# Teensy4_1.net
KiCad netlist of a schematic drawn in Altium Designer
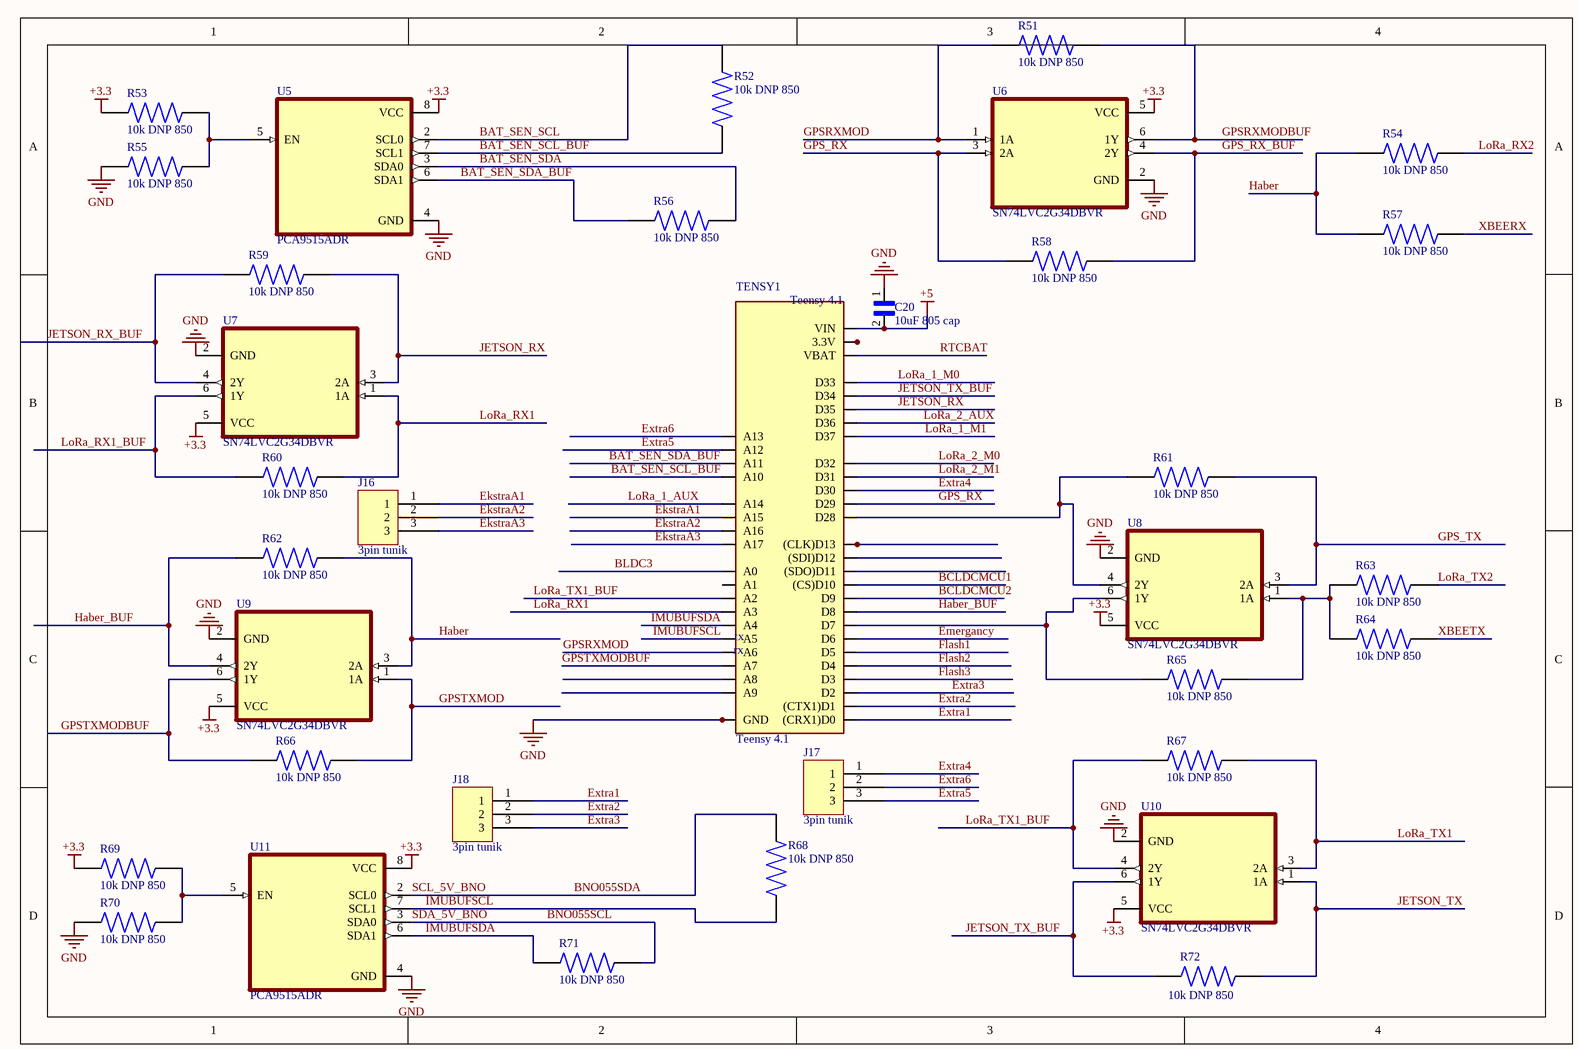
[diagram p0: Teensy4.1.SchDoc]

(export (version "E")
  (design (tool "Eeschema 10.0.6"))
  (components
    (comp (ref "C20")
      (value "10uF 805 cap")
      (footprint "1uF 805 Cap")
      (libsource (lib "iee_altium") (part "1uF 805 cap"))
    )
    (comp (ref "J16")
      (value "3pin tunik")
      (footprint "3pin tunik")
      (libsource (lib "iee_altium") (part "3pin tunik"))
    )
    (comp (ref "J17")
      (value "3pin tunik")
      (footprint "3pin tunik")
      (libsource (lib "iee_altium") (part "3pin tunik"))
    )
    (comp (ref "J18")
      (value "3pin tunik")
      (footprint "3pin tunik")
      (libsource (lib "iee_altium") (part "3pin tunik"))
    )
    (comp (ref "R51")
      (value "10k DNP 850")
      (footprint "10k 850")
      (libsource (lib "iee_altium") (part "10k 850"))
    )
    (comp (ref "R52")
      (value "10k DNP 850")
      (footprint "10k 850")
      (libsource (lib "iee_altium") (part "10k 850"))
    )
    (comp (ref "R53")
      (value "10k DNP 850")
      (footprint "10k 850")
      (libsource (lib "iee_altium") (part "10k 850"))
    )
    (comp (ref "R54")
      (value "10k DNP 850")
      (footprint "10k 850")
      (libsource (lib "iee_altium") (part "10k 850"))
    )
    (comp (ref "R55")
      (value "10k DNP 850")
      (footprint "10k 850")
      (libsource (lib "iee_altium") (part "10k 850"))
    )
    (comp (ref "R56")
      (value "10k DNP 850")
      (footprint "10k 850")
      (libsource (lib "iee_altium") (part "10k 850"))
    )
    (comp (ref "R57")
      (value "10k DNP 850")
      (footprint "10k 850")
      (libsource (lib "iee_altium") (part "10k 850"))
    )
    (comp (ref "R58")
      (value "10k DNP 850")
      (footprint "10k 850")
      (libsource (lib "iee_altium") (part "10k 850"))
    )
    (comp (ref "R59")
      (value "10k DNP 850")
      (footprint "10k 850")
      (libsource (lib "iee_altium") (part "10k 850"))
    )
    (comp (ref "R60")
      (value "10k DNP 850")
      (footprint "10k 850")
      (libsource (lib "iee_altium") (part "10k 850"))
    )
    (comp (ref "R61")
      (value "10k DNP 850")
      (footprint "10k 850")
      (libsource (lib "iee_altium") (part "10k 850"))
    )
    (comp (ref "R62")
      (value "10k DNP 850")
      (footprint "10k 850")
      (libsource (lib "iee_altium") (part "10k 850"))
    )
    (comp (ref "R63")
      (value "10k DNP 850")
      (footprint "10k 850")
      (libsource (lib "iee_altium") (part "10k 850"))
    )
    (comp (ref "R64")
      (value "10k DNP 850")
      (footprint "10k 850")
      (libsource (lib "iee_altium") (part "10k 850"))
    )
    (comp (ref "R65")
      (value "10k DNP 850")
      (footprint "10k 850")
      (libsource (lib "iee_altium") (part "10k 850"))
    )
    (comp (ref "R66")
      (value "10k DNP 850")
      (footprint "10k 850")
      (libsource (lib "iee_altium") (part "10k 850"))
    )
    (comp (ref "R67")
      (value "10k DNP 850")
      (footprint "10k 850")
      (libsource (lib "iee_altium") (part "10k 850"))
    )
    (comp (ref "R68")
      (value "10k DNP 850")
      (footprint "10k 850")
      (libsource (lib "iee_altium") (part "10k 850"))
    )
    (comp (ref "R69")
      (value "10k DNP 850")
      (footprint "10k 850")
      (libsource (lib "iee_altium") (part "10k 850"))
    )
    (comp (ref "R70")
      (value "10k DNP 850")
      (footprint "10k 850")
      (libsource (lib "iee_altium") (part "10k 850"))
    )
    (comp (ref "R71")
      (value "10k DNP 850")
      (footprint "10k 850")
      (libsource (lib "iee_altium") (part "10k 850"))
    )
    (comp (ref "R72")
      (value "10k DNP 850")
      (footprint "10k 850")
      (libsource (lib "iee_altium") (part "10k 850"))
    )
    (comp (ref "TENSY1")
      (value "Teensy 4.1")
      (footprint "Teensy 4.1")
      (libsource (lib "IEEE_altium") (part "Teensy 4.1"))
    )
    (comp (ref "U5")
      (value "PCA9515ADR")
      (footprint "SOIC127P599X175-8N")
      (description "Dual Bidirectional I2C Bus and SMBus Repeater 8-SOIC -40 to 85")
      (fields (field (name "MF") "Texas Instruments"))
      (libsource (lib "iee_altium") (part "PCA9515ADR"))
    )
    (comp (ref "U6")
      (value "SN74LVC2G34DBVR")
      (footprint "SOT95P280X145-6N")
      (description "2-ch, 1.65-V to 5.5-V buffers")
      (fields (field (name "MF") "Texas Instruments"))
      (libsource (lib "") (part "SN74LVC2G34DBVR_1"))
    )
    (comp (ref "U7")
      (value "SN74LVC2G34DBVR")
      (footprint "SOT95P280X145-6N")
      (description "2-ch, 1.65-V to 5.5-V buffers")
      (fields (field (name "MF") "Texas Instruments"))
      (libsource (lib "iee_altium") (part "SN74LVC2G34DBVR"))
    )
    (comp (ref "U8")
      (value "SN74LVC2G34DBVR")
      (footprint "SOT95P280X145-6N")
      (description "2-ch, 1.65-V to 5.5-V buffers")
      (fields (field (name "MF") "Texas Instruments"))
      (libsource (lib "iee_altium") (part "SN74LVC2G34DBVR"))
    )
    (comp (ref "U9")
      (value "SN74LVC2G34DBVR")
      (footprint "SOT95P280X145-6N")
      (description "2-ch, 1.65-V to 5.5-V buffers")
      (fields (field (name "MF") "Texas Instruments"))
      (libsource (lib "iee_altium") (part "SN74LVC2G34DBVR"))
    )
    (comp (ref "U10")
      (value "SN74LVC2G34DBVR")
      (footprint "SOT95P280X145-6N")
      (description "2-ch, 1.65-V to 5.5-V buffers")
      (fields (field (name "MF") "Texas Instruments"))
      (libsource (lib "iee_altium") (part "SN74LVC2G34DBVR"))
    )
    (comp (ref "U11")
      (value "PCA9515ADR")
      (footprint "SOIC127P599X175-8N")
      (description "Dual Bidirectional I2C Bus and SMBus Repeater 8-SOIC -40 to 85")
      (fields (field (name "MF") "Texas Instruments"))
      (libsource (lib "iee_altium") (part "PCA9515ADR"))
    )
  )
  (nets
    (net (code "1") (name "+3.3") (class "Default")
      (node (ref "R53") (pin "1") (pinfunction "1_1") (pintype "passive"))
      (node (ref "R69") (pin "1") (pinfunction "1_1") (pintype "passive"))
      (node (ref "U10") (pin "5") (pinfunction "VCC_5") (pintype "power_in"))
      (node (ref "U11") (pin "8") (pinfunction "VCC_8") (pintype "power_in"))
      (node (ref "U5") (pin "8") (pinfunction "VCC_8") (pintype "power_in"))
      (node (ref "U6") (pin "5") (pinfunction "VCC_5") (pintype "power_in"))
      (node (ref "U7") (pin "5") (pinfunction "VCC_5") (pintype "power_in"))
      (node (ref "U8") (pin "5") (pinfunction "VCC_5") (pintype "power_in"))
      (node (ref "U9") (pin "5") (pinfunction "VCC_5") (pintype "power_in"))
    )
    (net (code "2") (name "+5") (class "Default")
      (node (ref "C20") (pin "2") (pinfunction "2_2") (pintype "passive"))
      (node (ref "TENSY1") (pin "VIN") (pinfunction "VIN_VIN") (pintype "power_in"))
    )
    (net (code "3") (name "/BAT_SEN_SCL") (class "Default")
      (node (ref "R52") (pin "1") (pinfunction "1_1") (pintype "passive"))
      (node (ref "U5") (pin "2") (pinfunction "SCL0_2") (pintype "output"))
    )
    (net (code "4") (name "/BAT_SEN_SCL_BUF") (class "Default")
      (node (ref "R52") (pin "2") (pinfunction "2_2") (pintype "passive"))
      (node (ref "TENSY1") (pin "D24") (pinfunction "A10_D24") (pintype "bidirectional"))
      (node (ref "U5") (pin "7") (pinfunction "SCL1_7") (pintype "output"))
    )
    (net (code "5") (name "/BAT_SEN_SDA") (class "Default")
      (node (ref "R56") (pin "2") (pinfunction "2_2") (pintype "passive"))
      (node (ref "U5") (pin "3") (pinfunction "SDA0_3") (pintype "output"))
    )
    (net (code "6") (name "/BAT_SEN_SDA_BUF") (class "Default")
      (node (ref "R56") (pin "1") (pinfunction "1_1") (pintype "passive"))
      (node (ref "TENSY1") (pin "D25") (pinfunction "A11_D25") (pintype "bidirectional"))
      (node (ref "U5") (pin "6") (pinfunction "SDA1_6") (pintype "output"))
    )
    (net (code "7") (name "/BCLDCMCU1") (class "Default")
      (node (ref "TENSY1") (pin "D10") (pinfunction "(CS)D10_D10") (pintype "bidirectional"))
    )
    (net (code "8") (name "/BCLDCMCU2") (class "Default")
      (node (ref "TENSY1") (pin "D9") (pinfunction "D9_D9") (pintype "bidirectional"))
    )
    (net (code "9") (name "/BLDC3") (class "Default")
      (node (ref "TENSY1") (pin "D14") (pinfunction "A0_D14") (pintype "bidirectional"))
    )
    (net (code "10") (name "/BNO055SCL") (class "Default")
      (node (ref "R71") (pin "2") (pinfunction "2_2") (pintype "passive"))
      (node (ref "U11") (pin "3") (pinfunction "SDA0_3") (pintype "output"))
    )
    (net (code "11") (name "/BNO055SDA") (class "Default")
      (node (ref "R68") (pin "1") (pinfunction "1_1") (pintype "passive"))
      (node (ref "U11") (pin "2") (pinfunction "SCL0_2") (pintype "output"))
    )
    (net (code "12") (name "/EkstraA1") (class "Default")
      (node (ref "J16") (pin "1") (pinfunction "1_1") (pintype "passive"))
      (node (ref "TENSY1") (pin "D39") (pinfunction "A15_D39") (pintype "bidirectional"))
    )
    (net (code "13") (name "/EkstraA2") (class "Default")
      (node (ref "J16") (pin "2") (pinfunction "2_2") (pintype "passive"))
      (node (ref "TENSY1") (pin "D40") (pinfunction "A16_D40") (pintype "bidirectional"))
    )
    (net (code "14") (name "/EkstraA3") (class "Default")
      (node (ref "J16") (pin "3") (pinfunction "3_3") (pintype "passive"))
      (node (ref "TENSY1") (pin "D41") (pinfunction "A17_D41") (pintype "bidirectional"))
    )
    (net (code "15") (name "/Emergancy") (class "Default")
      (node (ref "TENSY1") (pin "D6") (pinfunction "D6_D6") (pintype "bidirectional"))
    )
    (net (code "16") (name "/Extra1") (class "Default")
      (node (ref "J18") (pin "1") (pinfunction "1_1") (pintype "passive"))
      (node (ref "TENSY1") (pin "D0") (pinfunction "(CRX1)D0_D0") (pintype "bidirectional"))
    )
    (net (code "17") (name "/Extra2") (class "Default")
      (node (ref "J18") (pin "2") (pinfunction "2_2") (pintype "passive"))
      (node (ref "TENSY1") (pin "D1") (pinfunction "(CTX1)D1_D1") (pintype "bidirectional"))
    )
    (net (code "18") (name "/Extra3") (class "Default")
      (node (ref "J18") (pin "3") (pinfunction "3_3") (pintype "passive"))
      (node (ref "TENSY1") (pin "D2") (pinfunction "D2_D2") (pintype "bidirectional"))
    )
    (net (code "19") (name "/Extra4") (class "Default")
      (node (ref "J17") (pin "1") (pinfunction "1_1") (pintype "passive"))
      (node (ref "TENSY1") (pin "D30") (pinfunction "D30_D30") (pintype "bidirectional"))
    )
    (net (code "20") (name "/Extra5") (class "Default")
      (node (ref "J17") (pin "3") (pinfunction "3_3") (pintype "passive"))
      (node (ref "TENSY1") (pin "D26") (pinfunction "A12_D26") (pintype "bidirectional"))
    )
    (net (code "21") (name "/Extra6") (class "Default")
      (node (ref "J17") (pin "2") (pinfunction "2_2") (pintype "passive"))
      (node (ref "TENSY1") (pin "D27") (pinfunction "A13_D27") (pintype "bidirectional"))
    )
    (net (code "22") (name "/Flash1") (class "Default")
      (node (ref "TENSY1") (pin "D5") (pinfunction "D5_D5") (pintype "bidirectional"))
    )
    (net (code "23") (name "/Flash2") (class "Default")
      (node (ref "TENSY1") (pin "D4") (pinfunction "D4_D4") (pintype "bidirectional"))
    )
    (net (code "24") (name "/Flash3") (class "Default")
      (node (ref "TENSY1") (pin "D3") (pinfunction "D3_D3") (pintype "bidirectional"))
    )
    (net (code "25") (name "/GPSRXMOD") (class "Default")
      (node (ref "R51") (pin "1") (pinfunction "1_1") (pintype "passive"))
      (node (ref "TENSY1") (pin "D20") (pinfunction "A6_D20") (pintype "bidirectional"))
      (node (ref "U6") (pin "1") (pinfunction "1A_1") (pintype "input"))
    )
    (net (code "26") (name "/GPSRXMODBUF") (class "Default")
      (node (ref "R51") (pin "2") (pinfunction "2_2") (pintype "passive"))
      (node (ref "U6") (pin "6") (pinfunction "1Y_6") (pintype "output"))
    )
    (net (code "27") (name "/GPSTXMOD") (class "Default")
      (node (ref "R66") (pin "2") (pinfunction "2_2") (pintype "passive"))
      (node (ref "U9") (pin "1") (pinfunction "1A_1") (pintype "input"))
    )
    (net (code "28") (name "/GPSTXMODBUF") (class "Default")
      (node (ref "R66") (pin "1") (pinfunction "1_1") (pintype "passive"))
      (node (ref "TENSY1") (pin "D21") (pinfunction "A7_D21") (pintype "bidirectional"))
      (node (ref "U9") (pin "6") (pinfunction "1Y_6") (pintype "output"))
    )
    (net (code "29") (name "/GPS_RX") (class "Default")
      (node (ref "R58") (pin "1") (pinfunction "1_1") (pintype "passive"))
      (node (ref "TENSY1") (pin "D29") (pinfunction "D29_D29") (pintype "bidirectional"))
      (node (ref "U6") (pin "3") (pinfunction "2A_3") (pintype "input"))
    )
    (net (code "30") (name "/GPS_RX_BUF") (class "Default")
      (node (ref "R58") (pin "2") (pinfunction "2_2") (pintype "passive"))
      (node (ref "U6") (pin "4") (pinfunction "2Y_4") (pintype "output"))
    )
    (net (code "31") (name "/GPS_TX") (class "Default")
      (node (ref "R61") (pin "2") (pinfunction "2_2") (pintype "passive"))
      (node (ref "U8") (pin "3") (pinfunction "2A_3") (pintype "input"))
    )
    (net (code "32") (name "/Haber") (class "Default")
      (node (ref "R54") (pin "1") (pinfunction "1_1") (pintype "passive"))
      (node (ref "R57") (pin "1") (pinfunction "1_1") (pintype "passive"))
      (node (ref "R62") (pin "2") (pinfunction "2_2") (pintype "passive"))
      (node (ref "U9") (pin "3") (pinfunction "2A_3") (pintype "input"))
    )
    (net (code "33") (name "/Haber_BUF") (class "Default")
      (node (ref "R62") (pin "1") (pinfunction "1_1") (pintype "passive"))
      (node (ref "TENSY1") (pin "D8") (pinfunction "D8_D8") (pintype "bidirectional"))
      (node (ref "U9") (pin "4") (pinfunction "2Y_4") (pintype "output"))
    )
    (net (code "34") (name "/IMUBUFSCL") (class "Default")
      (node (ref "R68") (pin "2") (pinfunction "2_2") (pintype "passive"))
      (node (ref "TENSY1") (pin "D19") (pinfunction "A5_D19") (pintype "bidirectional"))
      (node (ref "U11") (pin "7") (pinfunction "SCL1_7") (pintype "output"))
    )
    (net (code "35") (name "/IMUBUFSDA") (class "Default")
      (node (ref "R71") (pin "1") (pinfunction "1_1") (pintype "passive"))
      (node (ref "TENSY1") (pin "D18") (pinfunction "A4_D18") (pintype "bidirectional"))
      (node (ref "U11") (pin "6") (pinfunction "SDA1_6") (pintype "output"))
    )
    (net (code "36") (name "/JETSON_RX") (class "Default")
      (node (ref "R59") (pin "2") (pinfunction "2_2") (pintype "passive"))
      (node (ref "TENSY1") (pin "D35") (pinfunction "D35_D35") (pintype "bidirectional"))
      (node (ref "U7") (pin "3") (pinfunction "2A_3") (pintype "input"))
    )
    (net (code "37") (name "/JETSON_RX_BUF") (class "Default")
      (node (ref "R59") (pin "1") (pinfunction "1_1") (pintype "passive"))
      (node (ref "U7") (pin "4") (pinfunction "2Y_4") (pintype "output"))
    )
    (net (code "38") (name "/JETSON_TX") (class "Default")
      (node (ref "R72") (pin "2") (pinfunction "2_2") (pintype "passive"))
      (node (ref "U10") (pin "1") (pinfunction "1A_1") (pintype "input"))
    )
    (net (code "39") (name "/JETSON_TX_BUF") (class "Default")
      (node (ref "R72") (pin "1") (pinfunction "1_1") (pintype "passive"))
      (node (ref "TENSY1") (pin "D34") (pinfunction "D34_D34") (pintype "bidirectional"))
      (node (ref "U10") (pin "6") (pinfunction "1Y_6") (pintype "output"))
    )
    (net (code "40") (name "/LoRa_1_AUX") (class "Default")
      (node (ref "TENSY1") (pin "D38") (pinfunction "A14_D38") (pintype "bidirectional"))
    )
    (net (code "41") (name "/LoRa_1_M0") (class "Default")
      (node (ref "TENSY1") (pin "D33") (pinfunction "D33_D33") (pintype "bidirectional"))
    )
    (net (code "42") (name "/LoRa_1_M1") (class "Default")
      (node (ref "TENSY1") (pin "D37") (pinfunction "D37_D37") (pintype "bidirectional"))
    )
    (net (code "43") (name "/LoRa_2_AUX") (class "Default")
      (node (ref "TENSY1") (pin "D36") (pinfunction "D36_D36") (pintype "bidirectional"))
    )
    (net (code "44") (name "/LoRa_2_M0") (class "Default")
      (node (ref "TENSY1") (pin "D32") (pinfunction "D32_D32") (pintype "bidirectional"))
    )
    (net (code "45") (name "/LoRa_2_M1") (class "Default")
      (node (ref "TENSY1") (pin "D31") (pinfunction "D31_D31") (pintype "bidirectional"))
    )
    (net (code "46") (name "/LoRa_RX1") (class "Default")
      (node (ref "R60") (pin "2") (pinfunction "2_2") (pintype "passive"))
      (node (ref "TENSY1") (pin "D17") (pinfunction "A3_D17") (pintype "bidirectional"))
      (node (ref "U7") (pin "1") (pinfunction "1A_1") (pintype "input"))
    )
    (net (code "47") (name "/LoRa_RX1_BUF") (class "Default")
      (node (ref "R60") (pin "1") (pinfunction "1_1") (pintype "passive"))
      (node (ref "U7") (pin "6") (pinfunction "1Y_6") (pintype "output"))
    )
    (net (code "48") (name "/LoRa_RX2") (class "Default")
      (node (ref "R54") (pin "2") (pinfunction "2_2") (pintype "passive"))
    )
    (net (code "49") (name "/LoRa_TX1") (class "Default")
      (node (ref "R67") (pin "2") (pinfunction "2_2") (pintype "passive"))
      (node (ref "U10") (pin "3") (pinfunction "2A_3") (pintype "input"))
    )
    (net (code "50") (name "/LoRa_TX1_BUF") (class "Default")
      (node (ref "R67") (pin "1") (pinfunction "1_1") (pintype "passive"))
      (node (ref "TENSY1") (pin "D16") (pinfunction "A2_D16") (pintype "bidirectional"))
      (node (ref "U10") (pin "4") (pinfunction "2Y_4") (pintype "output"))
    )
    (net (code "51") (name "/LoRa_TX2") (class "Default")
      (node (ref "R63") (pin "2") (pinfunction "2_2") (pintype "passive"))
    )
    (net (code "52") (name "/RTCBAT") (class "Default")
      (node (ref "TENSY1") (pin "VBAT") (pinfunction "VBAT_VBAT") (pintype "power_in"))
    )
    (net (code "53") (name "/XBEERX") (class "Default")
      (node (ref "R57") (pin "2") (pinfunction "2_2") (pintype "passive"))
    )
    (net (code "54") (name "/XBEETX") (class "Default")
      (node (ref "R64") (pin "2") (pinfunction "2_2") (pintype "passive"))
    )
    (net (code "55") (name "GND") (class "Default")
      (node (ref "C20") (pin "1") (pinfunction "1_1") (pintype "passive"))
      (node (ref "R55") (pin "1") (pinfunction "1_1") (pintype "passive"))
      (node (ref "R70") (pin "1") (pinfunction "1_1") (pintype "passive"))
      (node (ref "TENSY1") (pin "AGND/GND") (pinfunction "GND_AGND/GND") (pintype "bidirectional"))
      (node (ref "TENSY1") (pin "GND") (pinfunction "GND_GND") (pintype "bidirectional"))
      (node (ref "TENSY1") (pin "GND@2") (pinfunction "GND_GND@2") (pintype "bidirectional"))
      (node (ref "U10") (pin "2") (pinfunction "GND_2") (pintype "power_in"))
      (node (ref "U11") (pin "4") (pinfunction "GND_4") (pintype "power_in"))
      (node (ref "U5") (pin "4") (pinfunction "GND_4") (pintype "power_in"))
      (node (ref "U6") (pin "2") (pinfunction "GND_2") (pintype "power_in"))
      (node (ref "U7") (pin "2") (pinfunction "GND_2") (pintype "power_in"))
      (node (ref "U8") (pin "2") (pinfunction "GND_2") (pintype "power_in"))
      (node (ref "U9") (pin "2") (pinfunction "GND_2") (pintype "power_in"))
    )
    (net (code "56") (name "Net-(TENSY1-3.3V-Pad3V3)") (class "Default")
      (node (ref "TENSY1") (pin "3V3") (pinfunction "3.3V_3V3") (pintype "power_in"))
      (node (ref "TENSY1") (pin "3V3@2") (pinfunction "3.3V_3V3@2") (pintype "power_in"))
      (node (ref "TENSY1") (pin "3V3@3") (pinfunction "3.3V_3V3@3") (pintype "power_in"))
    )
    (net (code "57") (name "Net-(U5-EN)") (class "Default")
      (node (ref "R53") (pin "2") (pinfunction "2_2") (pintype "passive"))
      (node (ref "R55") (pin "2") (pinfunction "2_2") (pintype "passive"))
      (node (ref "U5") (pin "5") (pinfunction "EN_5") (pintype "input"))
    )
    (net (code "58") (name "Net-(U8-1A)") (class "Default")
      (node (ref "R63") (pin "1") (pinfunction "1_1") (pintype "passive"))
      (node (ref "R64") (pin "1") (pinfunction "1_1") (pintype "passive"))
      (node (ref "R65") (pin "2") (pinfunction "2_2") (pintype "passive"))
      (node (ref "U8") (pin "1") (pinfunction "1A_1") (pintype "input"))
    )
    (net (code "59") (name "Net-(U8-1Y)") (class "Default")
      (node (ref "R65") (pin "1") (pinfunction "1_1") (pintype "passive"))
      (node (ref "TENSY1") (pin "D7") (pinfunction "D7_D7") (pintype "bidirectional"))
      (node (ref "U8") (pin "6") (pinfunction "1Y_6") (pintype "output"))
    )
    (net (code "60") (name "Net-(U8-2Y)") (class "Default")
      (node (ref "R61") (pin "1") (pinfunction "1_1") (pintype "passive"))
      (node (ref "TENSY1") (pin "D28") (pinfunction "D28_D28") (pintype "bidirectional"))
      (node (ref "U8") (pin "4") (pinfunction "2Y_4") (pintype "output"))
    )
    (net (code "61") (name "Net-(U11-EN)") (class "Default")
      (node (ref "R69") (pin "2") (pinfunction "2_2") (pintype "passive"))
      (node (ref "R70") (pin "2") (pinfunction "2_2") (pintype "passive"))
      (node (ref "U11") (pin "5") (pinfunction "EN_5") (pintype "input"))
    )
    (net (code "62") (name "unconnected-(TENSY1-(CLK)D13-PadD13)") (class "Default")
      (node (ref "TENSY1") (pin "D13") (pinfunction "(CLK)D13_D13") (pintype "bidirectional"))
    )
    (net (code "63") (name "unconnected-(TENSY1-(SDI)D12-PadD12)") (class "Default")
      (node (ref "TENSY1") (pin "D12") (pinfunction "(SDI)D12_D12") (pintype "bidirectional"))
    )
    (net (code "64") (name "unconnected-(TENSY1-(SDO)D11-PadD11)") (class "Default")
      (node (ref "TENSY1") (pin "D11") (pinfunction "(SDO)D11_D11") (pintype "bidirectional"))
    )
    (net (code "65") (name "unconnected-(TENSY1-A1-PadD15)") (class "Default")
      (node (ref "TENSY1") (pin "D15") (pinfunction "A1_D15") (pintype "bidirectional"))
    )
    (net (code "66") (name "unconnected-(TENSY1-A8-PadD22)") (class "Default")
      (node (ref "TENSY1") (pin "D22") (pinfunction "A8_D22") (pintype "bidirectional"))
    )
    (net (code "67") (name "unconnected-(TENSY1-A9-PadD23)") (class "Default")
      (node (ref "TENSY1") (pin "D23") (pinfunction "A9_D23") (pintype "bidirectional"))
    )
  )
)
